# Main.net
KiCad netlist of a schematic drawn in Altium Designer
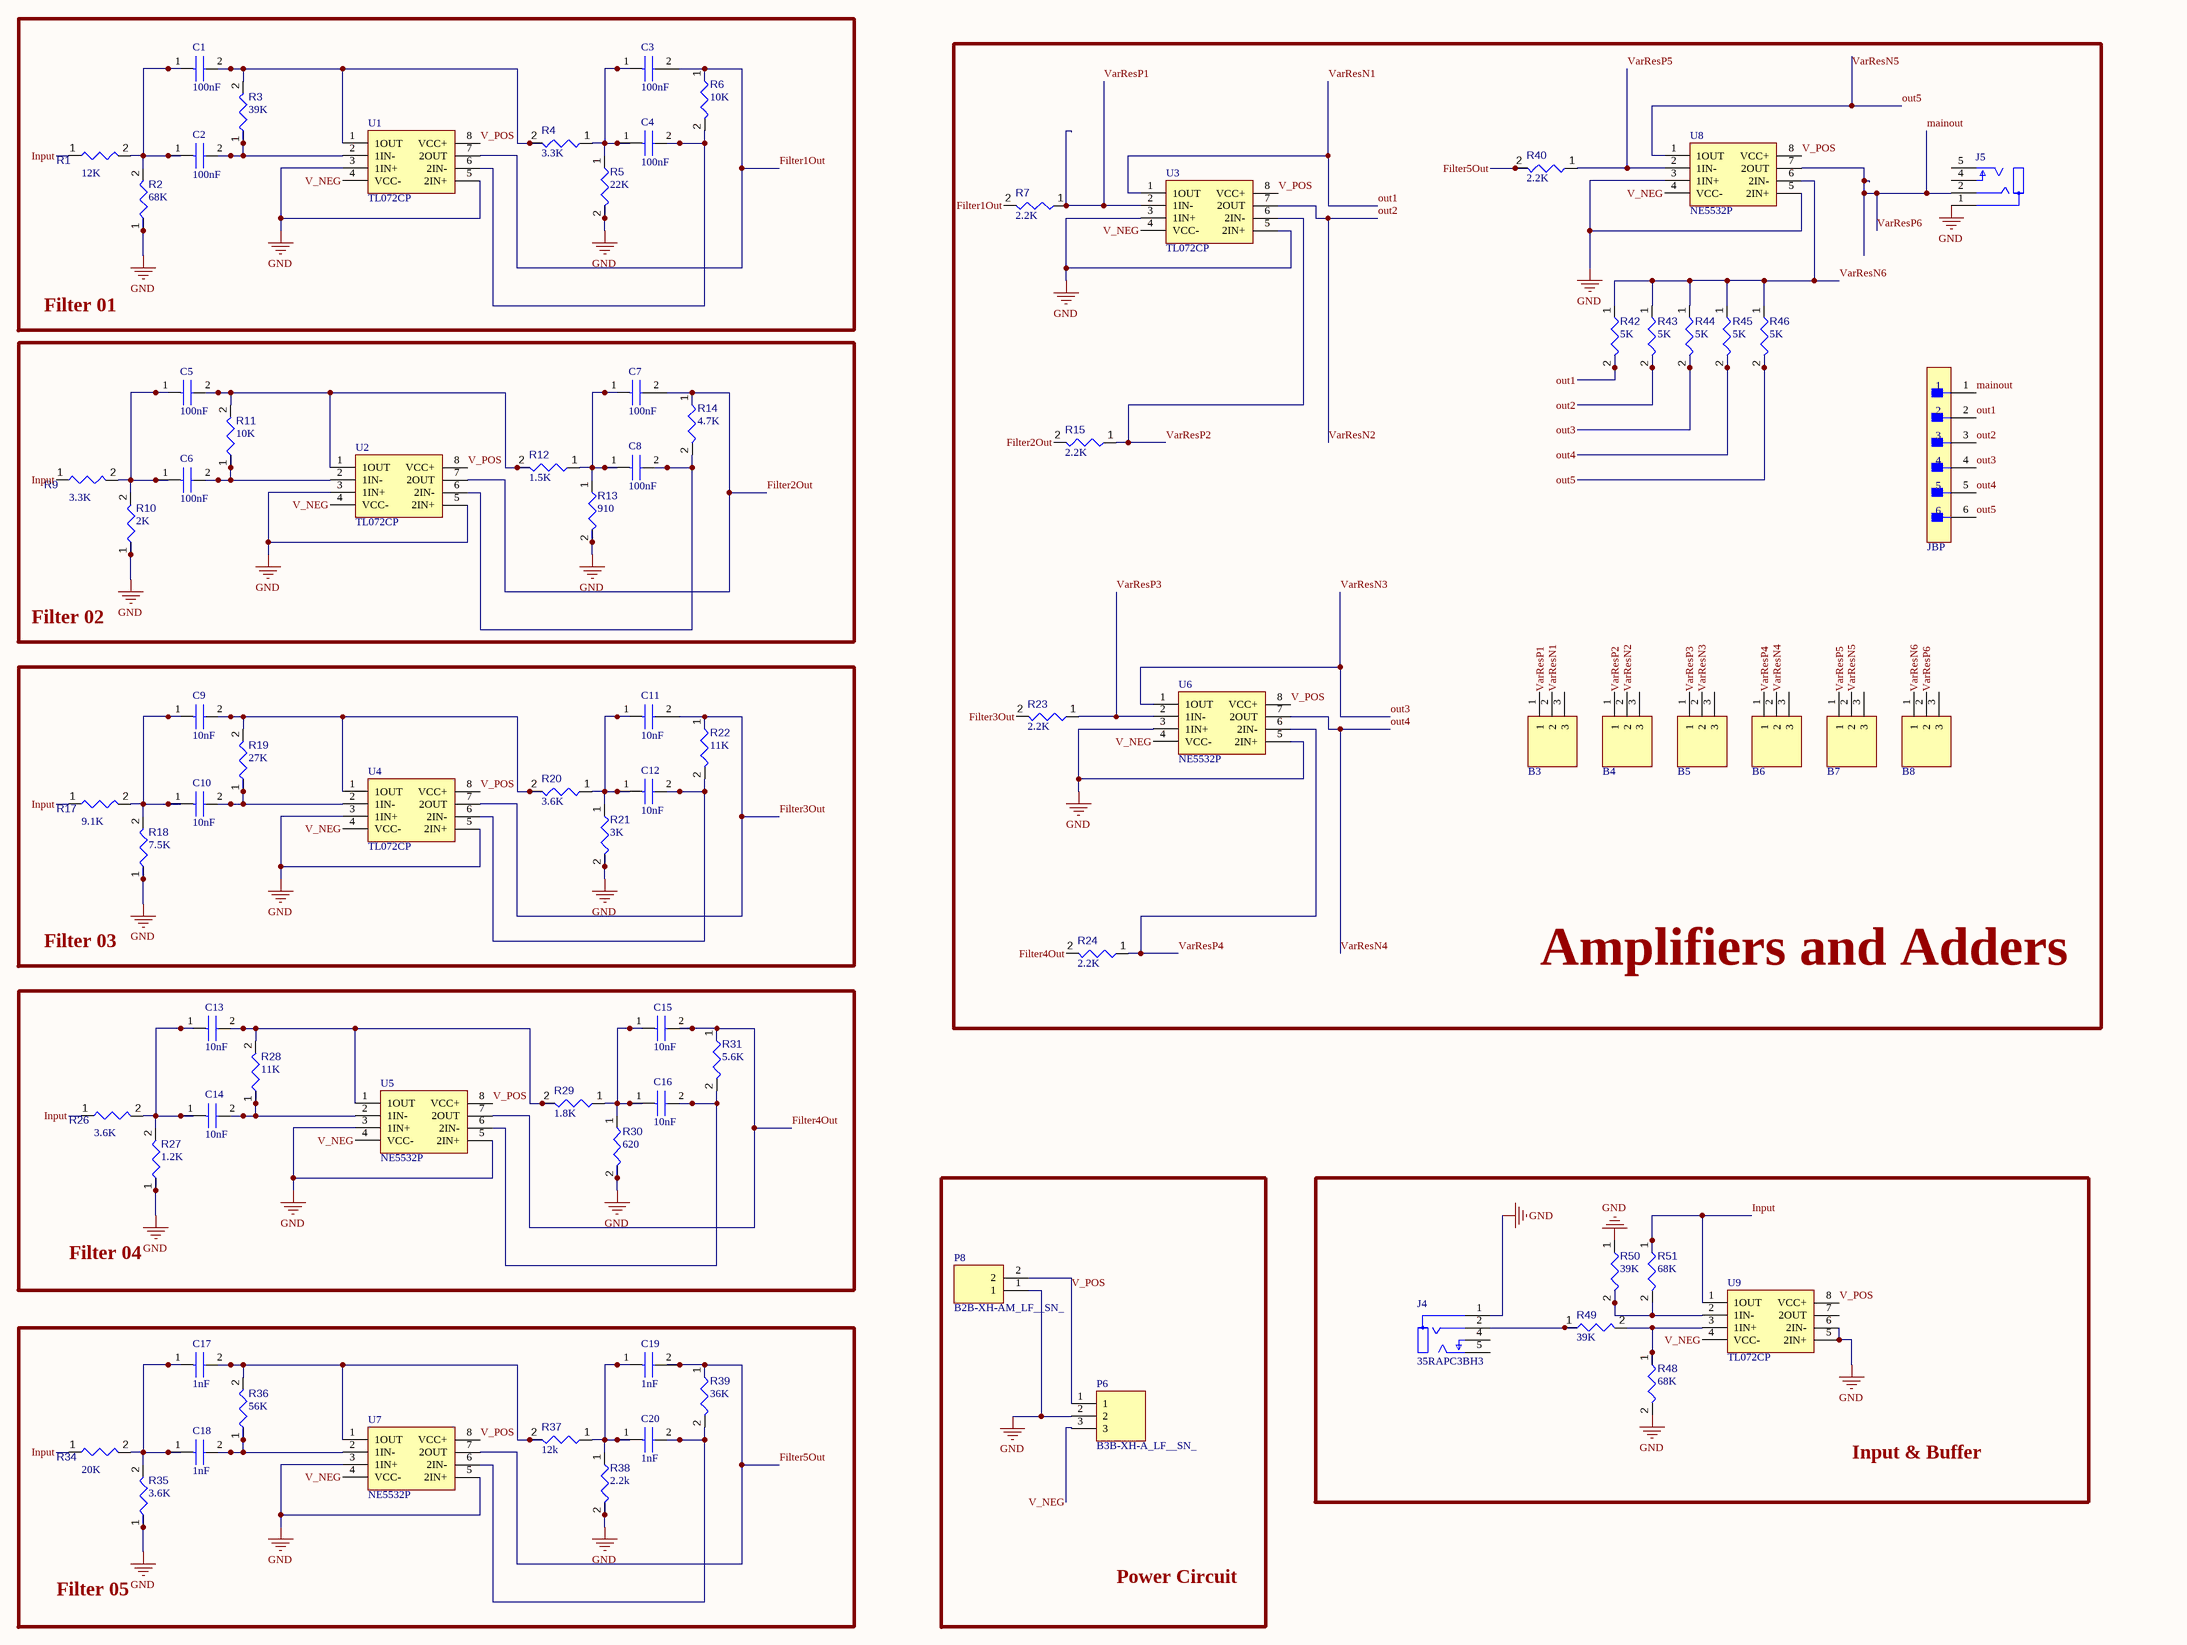
[diagram p0: Main.SchDoc]

(export (version "E")
  (design (tool "Eeschema 10.0.6"))
  (components
    (comp (ref "B3")
      (value "14910A0BHSX10502KA")
      (footprint "SamacSys:14910F0GJSX10103KA")
      (description "Variable Resistor")
      (fields (field (name "MOUSER PART NUMBER") "594-14910A0BHSP502KA"))
      (libsource (lib "*") (part "14910A0BHSX10502KA"))
    )
    (comp (ref "B4")
      (value "14910A0BHSX10502KA")
      (footprint "SamacSys:14910F0GJSX10103KA")
      (description "Variable Resistor")
      (fields (field (name "MOUSER PART NUMBER") "594-14910A0BHSP502KA"))
      (libsource (lib "*") (part "14910A0BHSX10502KA"))
    )
    (comp (ref "B5")
      (value "14910A0BHSX10502KA")
      (footprint "SamacSys:14910F0GJSX10103KA")
      (description "Variable Resistor")
      (fields (field (name "MOUSER PART NUMBER") "594-14910A0BHSP502KA"))
      (libsource (lib "*") (part "14910A0BHSX10502KA"))
    )
    (comp (ref "B6")
      (value "14910A0BHSX10502KA")
      (footprint "SamacSys:14910F0GJSX10103KA")
      (description "Variable Resistor")
      (fields (field (name "MOUSER PART NUMBER") "594-14910A0BHSP502KA"))
      (libsource (lib "*") (part "14910A0BHSX10502KA"))
    )
    (comp (ref "B7")
      (value "14910A0BHSX10502KA")
      (footprint "SamacSys:14910F0GJSX10103KA")
      (description "Variable Resistor")
      (fields (field (name "MOUSER PART NUMBER") "594-14910A0BHSP502KA"))
      (libsource (lib "*") (part "14910A0BHSX10502KA"))
    )
    (comp (ref "B8")
      (value "14910A0BHSX10502KA")
      (footprint "SamacSys:14910F0GJSX10103KA")
      (description "Variable Resistor")
      (fields (field (name "MOUSER PART NUMBER") "594-14910A0BHSP502KA"))
      (libsource (lib "*") (part "14910A0BHSX10502KA"))
    )
    (comp (ref "C1")
      (value "100nF")
      (footprint "SamacSys:K104K15X7RF5TL2")
      (description "Capacitor")
      (fields
        (field (name "MANUFACTURER_PART_NUMBER") "K104K15X7RF5TL2")
        (field (name "MOUSER PART NUMBER") "594-K104K15X7RF5TL2")
      )
      (libsource (lib "*") (part "K104K15X7RF5TL2"))
    )
    (comp (ref "C2")
      (value "100nF")
      (footprint "SamacSys:K104K15X7RF5TL2")
      (description "Capacitor")
      (fields
        (field (name "MANUFACTURER_PART_NUMBER") "K104K15X7RF5TL2")
        (field (name "MOUSER PART NUMBER") "594-K104K15X7RF5TL2")
      )
      (libsource (lib "*") (part "K104K15X7RF5TL2"))
    )
    (comp (ref "C3")
      (value "100nF")
      (footprint "SamacSys:K104K15X7RF5TL2")
      (description "Capacitor")
      (fields
        (field (name "MANUFACTURER_PART_NUMBER") "K104K15X7RF5TL2")
        (field (name "MOUSER PART NUMBER") "594-K104K15X7RF5TL2")
      )
      (libsource (lib "*") (part "K104K15X7RF5TL2"))
    )
    (comp (ref "C4")
      (value "100nF")
      (footprint "SamacSys:K104K15X7RF5TL2")
      (description "Capacitor")
      (fields
        (field (name "MANUFACTURER_PART_NUMBER") "K104K15X7RF5TL2")
        (field (name "MOUSER PART NUMBER") "594-K104K15X7RF5TL2")
      )
      (libsource (lib "*") (part "K104K15X7RF5TL2"))
    )
    (comp (ref "C5")
      (value "100nF")
      (footprint "SamacSys:K104K15X7RF5TL2")
      (description "Capacitor")
      (fields
        (field (name "MANUFACTURER_PART_NUMBER") "K104K15X7RF5TL2")
        (field (name "MOUSER PART NUMBER") "594-K104K15X7RF5TL2")
      )
      (libsource (lib "*") (part "K104K15X7RF5TL2"))
    )
    (comp (ref "C6")
      (value "100nF")
      (footprint "SamacSys:K104K15X7RF5TL2")
      (description "Capacitor")
      (fields
        (field (name "MANUFACTURER_PART_NUMBER") "K104K15X7RF5TL2")
        (field (name "MOUSER PART NUMBER") "594-K104K15X7RF5TL2")
      )
      (libsource (lib "*") (part "K104K15X7RF5TL2"))
    )
    (comp (ref "C7")
      (value "100nF")
      (footprint "SamacSys:K104K15X7RF5TL2")
      (description "Capacitor")
      (fields
        (field (name "MANUFACTURER_PART_NUMBER") "K104K15X7RF5TL2")
        (field (name "MOUSER PART NUMBER") "594-K104K15X7RF5TL2")
      )
      (libsource (lib "*") (part "K104K15X7RF5TL2"))
    )
    (comp (ref "C8")
      (value "100nF")
      (footprint "SamacSys:K104K15X7RF5TL2")
      (description "Capacitor")
      (fields
        (field (name "MANUFACTURER_PART_NUMBER") "K104K15X7RF5TL2")
        (field (name "MOUSER PART NUMBER") "594-K104K15X7RF5TL2")
      )
      (libsource (lib "*") (part "K104K15X7RF5TL2"))
    )
    (comp (ref "C9")
      (value "10nF")
      (footprint "SamacSys:K104K15X7RF5TL2")
      (description "Capacitor")
      (fields
        (field (name "MANUFACTURER_PART_NUMBER") "K104K15X7RF5TL2")
        (field (name "MOUSER PART NUMBER") "594-K104K15X7RF5TL2")
      )
      (libsource (lib "*") (part "K104K15X7RF5TL2"))
    )
    (comp (ref "C10")
      (value "10nF")
      (footprint "SamacSys:K104K15X7RF5TL2")
      (description "Capacitor")
      (fields
        (field (name "MANUFACTURER_PART_NUMBER") "K104K15X7RF5TL2")
        (field (name "MOUSER PART NUMBER") "594-K104K15X7RF5TL2")
      )
      (libsource (lib "*") (part "K104K15X7RF5TL2"))
    )
    (comp (ref "C11")
      (value "10nF")
      (footprint "SamacSys:K104K15X7RF5TL2")
      (description "Capacitor")
      (fields
        (field (name "MANUFACTURER_PART_NUMBER") "K104K15X7RF5TL2")
        (field (name "MOUSER PART NUMBER") "594-K104K15X7RF5TL2")
      )
      (libsource (lib "*") (part "K104K15X7RF5TL2"))
    )
    (comp (ref "C12")
      (value "10nF")
      (footprint "SamacSys:K104K15X7RF5TL2")
      (description "Capacitor")
      (fields
        (field (name "MANUFACTURER_PART_NUMBER") "K104K15X7RF5TL2")
        (field (name "MOUSER PART NUMBER") "594-K104K15X7RF5TL2")
      )
      (libsource (lib "*") (part "K104K15X7RF5TL2"))
    )
    (comp (ref "C13")
      (value "10nF")
      (footprint "SamacSys:K104K15X7RF5TL2")
      (description "Capacitor")
      (fields
        (field (name "MANUFACTURER_PART_NUMBER") "K104K15X7RF5TL2")
        (field (name "MOUSER PART NUMBER") "594-K104K15X7RF5TL2")
      )
      (libsource (lib "*") (part "K104K15X7RF5TL2"))
    )
    (comp (ref "C14")
      (value "10nF")
      (footprint "SamacSys:K104K15X7RF5TL2")
      (description "Capacitor")
      (fields
        (field (name "MANUFACTURER_PART_NUMBER") "K104K15X7RF5TL2")
        (field (name "MOUSER PART NUMBER") "594-K104K15X7RF5TL2")
      )
      (libsource (lib "*") (part "K104K15X7RF5TL2"))
    )
    (comp (ref "C15")
      (value "10nF")
      (footprint "SamacSys:K104K15X7RF5TL2")
      (description "Capacitor")
      (fields
        (field (name "MANUFACTURER_PART_NUMBER") "K104K15X7RF5TL2")
        (field (name "MOUSER PART NUMBER") "594-K104K15X7RF5TL2")
      )
      (libsource (lib "*") (part "K104K15X7RF5TL2"))
    )
    (comp (ref "C16")
      (value "10nF")
      (footprint "SamacSys:K104K15X7RF5TL2")
      (description "Capacitor")
      (fields
        (field (name "MANUFACTURER_PART_NUMBER") "K104K15X7RF5TL2")
        (field (name "MOUSER PART NUMBER") "594-K104K15X7RF5TL2")
      )
      (libsource (lib "*") (part "K104K15X7RF5TL2"))
    )
    (comp (ref "C17")
      (value "1nF")
      (footprint "SamacSys:K104K15X7RF5TL2")
      (description "Capacitor")
      (fields
        (field (name "MANUFACTURER_PART_NUMBER") "K104K15X7RF5TL2")
        (field (name "MOUSER PART NUMBER") "594-K104K15X7RF5TL2")
      )
      (libsource (lib "*") (part "K104K15X7RF5TL2"))
    )
    (comp (ref "C18")
      (value "1nF")
      (footprint "SamacSys:K104K15X7RF5TL2")
      (description "Capacitor")
      (fields
        (field (name "MANUFACTURER_PART_NUMBER") "K104K15X7RF5TL2")
        (field (name "MOUSER PART NUMBER") "594-K104K15X7RF5TL2")
      )
      (libsource (lib "*") (part "K104K15X7RF5TL2"))
    )
    (comp (ref "C19")
      (value "1nF")
      (footprint "SamacSys:K104K15X7RF5TL2")
      (description "Capacitor")
      (fields
        (field (name "MANUFACTURER_PART_NUMBER") "K104K15X7RF5TL2")
        (field (name "MOUSER PART NUMBER") "594-K104K15X7RF5TL2")
      )
      (libsource (lib "*") (part "K104K15X7RF5TL2"))
    )
    (comp (ref "C20")
      (value "1nF")
      (footprint "SamacSys:K104K15X7RF5TL2")
      (description "Capacitor")
      (fields
        (field (name "MANUFACTURER_PART_NUMBER") "K104K15X7RF5TL2")
        (field (name "MOUSER PART NUMBER") "594-K104K15X7RF5TL2")
      )
      (libsource (lib "*") (part "K104K15X7RF5TL2"))
    )
    (comp (ref "J4")
      (value "35RAPC3BH3")
      (footprint "FP-35RAPC3BH3-MFG")
      (description "CONN JACK STEREO 3.5MM R/A")
      (libsource (lib "Altium Content Vault") (part "6593a1246df2d7246a2ad7da18ee256"))
    )
    (comp (ref "J5")
      (value "35RAPC3BH3")
      (footprint "FP-35RAPC3BH3-MFG")
      (description "CONN JACK STEREO 3.5MM R/A")
      (libsource (lib "Altium Content Vault") (part "6593a1246df2d7246a2ad7da18ee256"))
    )
    (comp (ref "JBP")
      (value "B6B-XH-A(LF)(SN)")
      (footprint "FP-B6B-XH-A_LF_SN-MFG")
      (description "CONN HEADER VERT 6POS 2.5MM")
      (libsource (lib "Altium Content Vault") (part "f2cb566baf1c37ab5a3b8e90bbeafd6"))
    )
    (comp (ref "P6")
      (value "B3B-XH-A_LF__SN_")
      (footprint "SamacSys:B3BXHALFSN")
      (description "Connector")
      (fields (field (name "MANUFACTURER_PART_NUMBER") "B3B-XH-A(LF)(SN)"))
      (libsource (lib "*") (part "B3B-XH-A_LF__SN_"))
    )
    (comp (ref "P8")
      (value "B2B-XH-AM_LF__SN_")
      (footprint "SamacSys:B2BXHAMLFSN")
      (description "Connector")
      (fields (field (name "MANUFACTURER_PART_NUMBER") "B2B-XH-AM(LF)(SN)"))
      (libsource (lib "*") (part "B2B-XH-AM_LF__SN_"))
    )
    (comp (ref "R1")
      (value "12K")
      (footprint "RESA60-630X240")
      (description "Axial Resistor, 221 Ohm, +/- 1%, 250 mW, -55 to 155 degC, 2-Pin THD, RoHS, Bulk")
      (fields (field (name "TOLERANCE") "1%") (field (name "POWER") "250mW"))
      (libsource (lib "University of Moratuwa") (part "RES-2"))
    )
    (comp (ref "R2")
      (value "68K")
      (footprint "RESA60-630X240")
      (description "Axial Resistor, 221 Ohm, +/- 1%, 250 mW, -55 to 155 degC, 2-Pin THD, RoHS, Bulk")
      (fields (field (name "TOLERANCE") "1%") (field (name "POWER") "250mW"))
      (libsource (lib "University of Moratuwa") (part "RES-2"))
    )
    (comp (ref "R3")
      (value "39K")
      (footprint "RESA60-630X240")
      (description "Axial Resistor, 221 Ohm, +/- 1%, 250 mW, -55 to 155 degC, 2-Pin THD, RoHS, Bulk")
      (fields (field (name "TOLERANCE") "1%") (field (name "POWER") "250mW"))
      (libsource (lib "University of Moratuwa") (part "RES-2"))
    )
    (comp (ref "R4")
      (value "3.3K")
      (footprint "RESA60-630X240")
      (fields
        (field (name "TOLERANCE") "1%")
        (field (name "POWER") "250mW")
        (field (name "MANUFACTURER") "Yageo")
      )
      (libsource (lib "University of Moratuwa") (part "RES-2"))
    )
    (comp (ref "R5")
      (value "22K")
      (footprint "RESA60-630X240")
      (fields
        (field (name "TOLERANCE") "1%")
        (field (name "POWER") "250mW")
        (field (name "MANUFACTURER") "Yageo")
      )
      (libsource (lib "University of Moratuwa") (part "RES-2"))
    )
    (comp (ref "R6")
      (value "10K")
      (footprint "RESA60-630X240")
      (fields
        (field (name "TOLERANCE") "1%")
        (field (name "POWER") "250mW")
        (field (name "MANUFACTURER") "Yageo")
      )
      (libsource (lib "University of Moratuwa") (part "RES-2"))
    )
    (comp (ref "R7")
      (value "2.2K")
      (footprint "RESA60-630X240")
      (fields
        (field (name "TOLERANCE") "1%")
        (field (name "POWER") "250mW")
        (field (name "MANUFACTURER") "Yageo")
      )
      (libsource (lib "University of Moratuwa") (part "RES-2"))
    )
    (comp (ref "R9")
      (value "3.3K")
      (footprint "RESA60-630X240")
      (description "Axial Resistor, 221 Ohm, +/- 1%, 250 mW, -55 to 155 degC, 2-Pin THD, RoHS, Bulk")
      (fields (field (name "TOLERANCE") "1%") (field (name "POWER") "250mW"))
      (libsource (lib "University of Moratuwa") (part "RES-2"))
    )
    (comp (ref "R10")
      (value "2K")
      (footprint "RESA60-630X240")
      (description "Axial Resistor, 221 Ohm, +/- 1%, 250 mW, -55 to 155 degC, 2-Pin THD, RoHS, Bulk")
      (fields (field (name "TOLERANCE") "1%") (field (name "POWER") "250mW"))
      (libsource (lib "University of Moratuwa") (part "RES-2"))
    )
    (comp (ref "R11")
      (value "10K")
      (footprint "RESA60-630X240")
      (description "Axial Resistor, 221 Ohm, +/- 1%, 250 mW, -55 to 155 degC, 2-Pin THD, RoHS, Bulk")
      (fields (field (name "TOLERANCE") "1%") (field (name "POWER") "250mW"))
      (libsource (lib "University of Moratuwa") (part "RES-2"))
    )
    (comp (ref "R12")
      (value "1.5K")
      (footprint "RESA60-630X240")
      (fields
        (field (name "TOLERANCE") "1%")
        (field (name "POWER") "250mW")
        (field (name "MANUFACTURER") "Yageo")
      )
      (libsource (lib "University of Moratuwa") (part "RES-2"))
    )
    (comp (ref "R13")
      (value "910")
      (footprint "RESA60-630X240")
      (fields
        (field (name "TOLERANCE") "1%")
        (field (name "POWER") "250mW")
        (field (name "MANUFACTURER") "Yageo")
      )
      (libsource (lib "University of Moratuwa") (part "RES-2"))
    )
    (comp (ref "R14")
      (value "4.7K")
      (footprint "RESA60-630X240")
      (fields
        (field (name "TOLERANCE") "1%")
        (field (name "POWER") "250mW")
        (field (name "MANUFACTURER") "Yageo")
      )
      (libsource (lib "University of Moratuwa") (part "RES-2"))
    )
    (comp (ref "R15")
      (value "2.2K")
      (footprint "RESA60-630X240")
      (fields
        (field (name "TOLERANCE") "1%")
        (field (name "POWER") "250mW")
        (field (name "MANUFACTURER") "Yageo")
      )
      (libsource (lib "University of Moratuwa") (part "RES-2"))
    )
    (comp (ref "R17")
      (value "9.1K")
      (footprint "RESA60-630X240")
      (description "Axial Resistor, 221 Ohm, +/- 1%, 250 mW, -55 to 155 degC, 2-Pin THD, RoHS, Bulk")
      (fields (field (name "TOLERANCE") "1%") (field (name "POWER") "250mW"))
      (libsource (lib "University of Moratuwa") (part "RES-2"))
    )
    (comp (ref "R18")
      (value "7.5K")
      (footprint "RESA60-630X240")
      (description "Axial Resistor, 221 Ohm, +/- 1%, 250 mW, -55 to 155 degC, 2-Pin THD, RoHS, Bulk")
      (fields (field (name "TOLERANCE") "1%") (field (name "POWER") "250mW"))
      (libsource (lib "University of Moratuwa") (part "RES-2"))
    )
    (comp (ref "R19")
      (value "27K")
      (footprint "RESA60-630X240")
      (description "Axial Resistor, 221 Ohm, +/- 1%, 250 mW, -55 to 155 degC, 2-Pin THD, RoHS, Bulk")
      (fields (field (name "TOLERANCE") "1%") (field (name "POWER") "250mW"))
      (libsource (lib "University of Moratuwa") (part "RES-2"))
    )
    (comp (ref "R20")
      (value "3.6K")
      (footprint "RESA60-630X240")
      (fields
        (field (name "TOLERANCE") "1%")
        (field (name "POWER") "250mW")
        (field (name "MANUFACTURER") "Yageo")
      )
      (libsource (lib "University of Moratuwa") (part "RES-2"))
    )
    (comp (ref "R21")
      (value "3K")
      (footprint "RESA60-630X240")
      (fields
        (field (name "TOLERANCE") "1%")
        (field (name "POWER") "250mW")
        (field (name "MANUFACTURER") "Yageo")
      )
      (libsource (lib "University of Moratuwa") (part "RES-2"))
    )
    (comp (ref "R22")
      (value "11K")
      (footprint "RESA60-630X240")
      (fields
        (field (name "TOLERANCE") "1%")
        (field (name "POWER") "250mW")
        (field (name "MANUFACTURER") "Yageo")
      )
      (libsource (lib "University of Moratuwa") (part "RES-2"))
    )
    (comp (ref "R23")
      (value "2.2K")
      (footprint "RESA60-630X240")
      (fields
        (field (name "TOLERANCE") "1%")
        (field (name "POWER") "250mW")
        (field (name "MANUFACTURER") "Yageo")
      )
      (libsource (lib "University of Moratuwa") (part "RES-2"))
    )
    (comp (ref "R24")
      (value "2.2K")
      (footprint "RESA60-630X240")
      (fields
        (field (name "TOLERANCE") "1%")
        (field (name "POWER") "250mW")
        (field (name "MANUFACTURER") "Yageo")
      )
      (libsource (lib "University of Moratuwa") (part "RES-2"))
    )
    (comp (ref "R26")
      (value "3.6K")
      (footprint "RESA60-630X240")
      (description "Axial Resistor, 221 Ohm, +/- 1%, 250 mW, -55 to 155 degC, 2-Pin THD, RoHS, Bulk")
      (fields (field (name "TOLERANCE") "1%") (field (name "POWER") "250mW"))
      (libsource (lib "University of Moratuwa") (part "RES-2"))
    )
    (comp (ref "R27")
      (value "1.2K")
      (footprint "RESA60-630X240")
      (description "Axial Resistor, 221 Ohm, +/- 1%, 250 mW, -55 to 155 degC, 2-Pin THD, RoHS, Bulk")
      (fields (field (name "TOLERANCE") "1%") (field (name "POWER") "250mW"))
      (libsource (lib "University of Moratuwa") (part "RES-2"))
    )
    (comp (ref "R28")
      (value "11K")
      (footprint "RESA60-630X240")
      (description "Axial Resistor, 221 Ohm, +/- 1%, 250 mW, -55 to 155 degC, 2-Pin THD, RoHS, Bulk")
      (fields (field (name "TOLERANCE") "1%") (field (name "POWER") "250mW"))
      (libsource (lib "University of Moratuwa") (part "RES-2"))
    )
    (comp (ref "R29")
      (value "1.8K")
      (footprint "RESA60-630X240")
      (fields
        (field (name "TOLERANCE") "1%")
        (field (name "POWER") "250mW")
        (field (name "MANUFACTURER") "Yageo")
      )
      (libsource (lib "University of Moratuwa") (part "RES-2"))
    )
    (comp (ref "R30")
      (value "620")
      (footprint "RESA60-630X240")
      (fields
        (field (name "TOLERANCE") "1%")
        (field (name "POWER") "250mW")
        (field (name "MANUFACTURER") "Yageo")
      )
      (libsource (lib "University of Moratuwa") (part "RES-2"))
    )
    (comp (ref "R31")
      (value "5.6K")
      (footprint "RESA60-630X240")
      (fields
        (field (name "TOLERANCE") "1%")
        (field (name "POWER") "250mW")
        (field (name "MANUFACTURER") "Yageo")
      )
      (libsource (lib "University of Moratuwa") (part "RES-2"))
    )
    (comp (ref "R34")
      (value "20K")
      (footprint "RESA60-630X240")
      (description "Axial Resistor, 221 Ohm, +/- 1%, 250 mW, -55 to 155 degC, 2-Pin THD, RoHS, Bulk")
      (fields (field (name "TOLERANCE") "1%") (field (name "POWER") "250mW"))
      (libsource (lib "University of Moratuwa") (part "RES-2"))
    )
    (comp (ref "R35")
      (value "3.6K")
      (footprint "RESA60-630X240")
      (description "Axial Resistor, 221 Ohm, +/- 1%, 250 mW, -55 to 155 degC, 2-Pin THD, RoHS, Bulk")
      (fields (field (name "TOLERANCE") "1%") (field (name "POWER") "250mW"))
      (libsource (lib "University of Moratuwa") (part "RES-2"))
    )
    (comp (ref "R36")
      (value "56K")
      (footprint "RESA60-630X240")
      (description "Axial Resistor, 221 Ohm, +/- 1%, 250 mW, -55 to 155 degC, 2-Pin THD, RoHS, Bulk")
      (fields (field (name "TOLERANCE") "1%") (field (name "POWER") "250mW"))
      (libsource (lib "University of Moratuwa") (part "RES-2"))
    )
    (comp (ref "R37")
      (value "12k")
      (footprint "RESA60-630X240")
      (fields
        (field (name "TOLERANCE") "1%")
        (field (name "POWER") "250mW")
        (field (name "MANUFACTURER") "Yageo")
      )
      (libsource (lib "University of Moratuwa") (part "RES-2"))
    )
    (comp (ref "R38")
      (value "2.2k")
      (footprint "RESA60-630X240")
      (fields
        (field (name "TOLERANCE") "1%")
        (field (name "POWER") "250mW")
        (field (name "MANUFACTURER") "Yageo")
      )
      (libsource (lib "University of Moratuwa") (part "RES-2"))
    )
    (comp (ref "R39")
      (value "36K")
      (footprint "RESA60-630X240")
      (fields
        (field (name "TOLERANCE") "1%")
        (field (name "POWER") "250mW")
        (field (name "MANUFACTURER") "Yageo")
      )
      (libsource (lib "University of Moratuwa") (part "RES-2"))
    )
    (comp (ref "R40")
      (value "2.2K")
      (footprint "RESA60-630X240")
      (fields
        (field (name "TOLERANCE") "1%")
        (field (name "POWER") "250mW")
        (field (name "MANUFACTURER") "Yageo")
      )
      (libsource (lib "University of Moratuwa") (part "RES-2"))
    )
    (comp (ref "R42")
      (value "5K")
      (footprint "RESA60-630X240")
      (fields
        (field (name "TOLERANCE") "1%")
        (field (name "POWER") "250mW")
        (field (name "MANUFACTURER") "Yageo")
      )
      (libsource (lib "University of Moratuwa") (part "RES-2"))
    )
    (comp (ref "R43")
      (value "5K")
      (footprint "RESA60-630X240")
      (fields
        (field (name "TOLERANCE") "1%")
        (field (name "POWER") "250mW")
        (field (name "MANUFACTURER") "Yageo")
      )
      (libsource (lib "University of Moratuwa") (part "RES-2"))
    )
    (comp (ref "R44")
      (value "5K")
      (footprint "RESA60-630X240")
      (fields
        (field (name "TOLERANCE") "1%")
        (field (name "POWER") "250mW")
        (field (name "MANUFACTURER") "Yageo")
      )
      (libsource (lib "University of Moratuwa") (part "RES-2"))
    )
    (comp (ref "R45")
      (value "5K")
      (footprint "RESA60-630X240")
      (fields
        (field (name "TOLERANCE") "1%")
        (field (name "POWER") "250mW")
        (field (name "MANUFACTURER") "Yageo")
      )
      (libsource (lib "University of Moratuwa") (part "RES-2"))
    )
    (comp (ref "R46")
      (value "5K")
      (footprint "RESA60-630X240")
      (fields
        (field (name "TOLERANCE") "1%")
        (field (name "POWER") "250mW")
        (field (name "MANUFACTURER") "Yageo")
      )
      (libsource (lib "University of Moratuwa") (part "RES-2"))
    )
    (comp (ref "R48")
      (value "68K")
      (footprint "RESA60-630X240")
      (fields
        (field (name "TOLERANCE") "1%")
        (field (name "POWER") "250mW")
        (field (name "MANUFACTURER") "Yageo")
      )
      (libsource (lib "University of Moratuwa") (part "RES-2"))
    )
    (comp (ref "R49")
      (value "39K")
      (footprint "RESA60-630X240")
      (fields
        (field (name "TOLERANCE") "1%")
        (field (name "POWER") "250mW")
        (field (name "MANUFACTURER") "Yageo")
      )
      (libsource (lib "University of Moratuwa") (part "RES-2"))
    )
    (comp (ref "R50")
      (value "39K")
      (footprint "RESA60-630X240")
      (fields
        (field (name "TOLERANCE") "1%")
        (field (name "POWER") "250mW")
        (field (name "MANUFACTURER") "Yageo")
      )
      (libsource (lib "University of Moratuwa") (part "RES-2"))
    )
    (comp (ref "R51")
      (value "68K")
      (footprint "RESA60-630X240")
      (fields
        (field (name "TOLERANCE") "1%")
        (field (name "POWER") "250mW")
        (field (name "MANUFACTURER") "Yageo")
      )
      (libsource (lib "University of Moratuwa") (part "RES-2"))
    )
    (comp (ref "U1")
      (value "TL072CP")
      (footprint "SamacSys:DIP794W53P254L959H508Q8N")
      (description "Integrated Circuit")
      (fields (field (name "MOUSER PART NUMBER") "595-TL072CP"))
      (libsource (lib "*") (part "TL072CP"))
    )
    (comp (ref "U2")
      (value "TL072CP")
      (footprint "SamacSys:DIP794W53P254L959H508Q8N")
      (description "Integrated Circuit")
      (fields (field (name "MOUSER PART NUMBER") "595-TL072CP"))
      (libsource (lib "*") (part "TL072CP"))
    )
    (comp (ref "U3")
      (value "TL072CP")
      (footprint "SamacSys:DIP794W53P254L959H508Q8N")
      (description "Integrated Circuit")
      (fields (field (name "MOUSER PART NUMBER") "595-TL072CP"))
      (libsource (lib "*") (part "TL072CP"))
    )
    (comp (ref "U4")
      (value "TL072CP")
      (footprint "SamacSys:DIP794W53P254L959H508Q8N")
      (description "Integrated Circuit")
      (fields (field (name "MOUSER PART NUMBER") "595-TL072CP"))
      (libsource (lib "*") (part "TL072CP"))
    )
    (comp (ref "U5")
      (value "NE5532P")
      (footprint "SamacSys:DIP794W53P254L959H508Q8N")
      (description "Integrated Circuit")
      (fields (field (name "MOUSER PART NUMBER") "595-NE5532P"))
      (libsource (lib "*") (part "NE5532P"))
    )
    (comp (ref "U6")
      (value "NE5532P")
      (footprint "SamacSys:DIP794W53P254L959H508Q8N")
      (description "Integrated Circuit")
      (fields (field (name "MOUSER PART NUMBER") "595-NE5532P"))
      (libsource (lib "*") (part "NE5532P"))
    )
    (comp (ref "U7")
      (value "NE5532P")
      (footprint "SamacSys:DIP794W53P254L959H508Q8N")
      (description "Integrated Circuit")
      (fields (field (name "MOUSER PART NUMBER") "595-NE5532P"))
      (libsource (lib "*") (part "NE5532P"))
    )
    (comp (ref "U8")
      (value "NE5532P")
      (footprint "SamacSys:DIP794W53P254L959H508Q8N")
      (description "Integrated Circuit")
      (fields (field (name "MOUSER PART NUMBER") "595-NE5532P"))
      (libsource (lib "*") (part "NE5532P"))
    )
    (comp (ref "U9")
      (value "TL072CP")
      (footprint "SamacSys:DIP794W53P254L959H508Q8N")
      (description "Integrated Circuit")
      (fields (field (name "MOUSER PART NUMBER") "595-TL072CP"))
      (libsource (lib "*") (part "TL072CP"))
    )
  )
  (nets
    (net (code "1") (name "/Filter1Out") (class "Default")
      (node (ref "C3") (pin "2") (pinfunction "-_2") (pintype "passive"))
      (node (ref "R6") (pin "1") (pinfunction "1_1") (pintype "passive"))
      (node (ref "R7") (pin "2") (pinfunction "2_2") (pintype "passive"))
      (node (ref "U1") (pin "7") (pinfunction "2OUT_7") (pintype "passive"))
    )
    (net (code "2") (name "/Filter2Out") (class "Default")
      (node (ref "C7") (pin "2") (pinfunction "-_2") (pintype "passive"))
      (node (ref "R14") (pin "1") (pinfunction "1_1") (pintype "passive"))
      (node (ref "R15") (pin "2") (pinfunction "2_2") (pintype "passive"))
      (node (ref "U2") (pin "7") (pinfunction "2OUT_7") (pintype "passive"))
    )
    (net (code "3") (name "/Filter3Out") (class "Default")
      (node (ref "C11") (pin "2") (pinfunction "-_2") (pintype "passive"))
      (node (ref "R22") (pin "1") (pinfunction "1_1") (pintype "passive"))
      (node (ref "R23") (pin "2") (pinfunction "2_2") (pintype "passive"))
      (node (ref "U4") (pin "7") (pinfunction "2OUT_7") (pintype "passive"))
    )
    (net (code "4") (name "/Filter4Out") (class "Default")
      (node (ref "C15") (pin "2") (pinfunction "-_2") (pintype "passive"))
      (node (ref "R24") (pin "2") (pinfunction "2_2") (pintype "passive"))
      (node (ref "R31") (pin "1") (pinfunction "1_1") (pintype "passive"))
      (node (ref "U5") (pin "7") (pinfunction "2OUT_7") (pintype "passive"))
    )
    (net (code "5") (name "/Filter5Out") (class "Default")
      (node (ref "C19") (pin "2") (pinfunction "-_2") (pintype "passive"))
      (node (ref "R39") (pin "1") (pinfunction "1_1") (pintype "passive"))
      (node (ref "R40") (pin "2") (pinfunction "2_2") (pintype "passive"))
      (node (ref "U7") (pin "7") (pinfunction "2OUT_7") (pintype "passive"))
    )
    (net (code "6") (name "/Input") (class "Default")
      (node (ref "R1") (pin "1") (pinfunction "1_1") (pintype "passive"))
      (node (ref "R17") (pin "1") (pinfunction "1_1") (pintype "passive"))
      (node (ref "R26") (pin "1") (pinfunction "1_1") (pintype "passive"))
      (node (ref "R34") (pin "1") (pinfunction "1_1") (pintype "passive"))
      (node (ref "R51") (pin "1") (pinfunction "1_1") (pintype "passive"))
      (node (ref "R9") (pin "1") (pinfunction "1_1") (pintype "passive"))
      (node (ref "U9") (pin "1") (pinfunction "1OUT_1") (pintype "passive"))
    )
    (net (code "7") (name "/V_NEG") (class "Default")
      (node (ref "P6") (pin "3") (pinfunction "3_3") (pintype "passive"))
      (node (ref "U1") (pin "4") (pinfunction "VCC-_4") (pintype "passive"))
      (node (ref "U2") (pin "4") (pinfunction "VCC-_4") (pintype "passive"))
      (node (ref "U3") (pin "4") (pinfunction "VCC-_4") (pintype "passive"))
      (node (ref "U4") (pin "4") (pinfunction "VCC-_4") (pintype "passive"))
      (node (ref "U5") (pin "4") (pinfunction "VCC-_4") (pintype "passive"))
      (node (ref "U6") (pin "4") (pinfunction "VCC-_4") (pintype "passive"))
      (node (ref "U7") (pin "4") (pinfunction "VCC-_4") (pintype "passive"))
      (node (ref "U8") (pin "4") (pinfunction "VCC-_4") (pintype "passive"))
      (node (ref "U9") (pin "4") (pinfunction "VCC-_4") (pintype "passive"))
    )
    (net (code "8") (name "/V_POS") (class "Default")
      (node (ref "P6") (pin "1") (pinfunction "1_1") (pintype "passive"))
      (node (ref "P8") (pin "2") (pinfunction "2_2") (pintype "passive"))
      (node (ref "U1") (pin "8") (pinfunction "VCC+_8") (pintype "passive"))
      (node (ref "U2") (pin "8") (pinfunction "VCC+_8") (pintype "passive"))
      (node (ref "U3") (pin "8") (pinfunction "VCC+_8") (pintype "passive"))
      (node (ref "U4") (pin "8") (pinfunction "VCC+_8") (pintype "passive"))
      (node (ref "U5") (pin "8") (pinfunction "VCC+_8") (pintype "passive"))
      (node (ref "U6") (pin "8") (pinfunction "VCC+_8") (pintype "passive"))
      (node (ref "U7") (pin "8") (pinfunction "VCC+_8") (pintype "passive"))
      (node (ref "U8") (pin "8") (pinfunction "VCC+_8") (pintype "passive"))
      (node (ref "U9") (pin "8") (pinfunction "VCC+_8") (pintype "passive"))
    )
    (net (code "9") (name "/VarResN1") (class "Default")
      (node (ref "B3") (pin "2") (pinfunction "2_2") (pintype "passive"))
      (node (ref "JBP") (pin "2") (pinfunction "2_2") (pintype "passive"))
      (node (ref "R42") (pin "2") (pinfunction "2_2") (pintype "passive"))
      (node (ref "U3") (pin "1") (pinfunction "1OUT_1") (pintype "passive"))
    )
    (net (code "10") (name "/VarResN2") (class "Default")
      (node (ref "B4") (pin "2") (pinfunction "2_2") (pintype "passive"))
      (node (ref "JBP") (pin "3") (pinfunction "3_3") (pintype "passive"))
      (node (ref "R43") (pin "2") (pinfunction "2_2") (pintype "passive"))
      (node (ref "U3") (pin "7") (pinfunction "2OUT_7") (pintype "passive"))
    )
    (net (code "11") (name "/VarResN3") (class "Default")
      (node (ref "B5") (pin "2") (pinfunction "2_2") (pintype "passive"))
      (node (ref "JBP") (pin "4") (pinfunction "4_4") (pintype "passive"))
      (node (ref "R44") (pin "2") (pinfunction "2_2") (pintype "passive"))
      (node (ref "U6") (pin "1") (pinfunction "1OUT_1") (pintype "passive"))
    )
    (net (code "12") (name "/VarResN4") (class "Default")
      (node (ref "B6") (pin "2") (pinfunction "2_2") (pintype "passive"))
      (node (ref "JBP") (pin "5") (pinfunction "5_5") (pintype "passive"))
      (node (ref "R45") (pin "2") (pinfunction "2_2") (pintype "passive"))
      (node (ref "U6") (pin "7") (pinfunction "2OUT_7") (pintype "passive"))
    )
    (net (code "13") (name "/VarResN5") (class "Default")
      (node (ref "B7") (pin "2") (pinfunction "2_2") (pintype "passive"))
      (node (ref "JBP") (pin "6") (pinfunction "6_6") (pintype "passive"))
      (node (ref "R46") (pin "2") (pinfunction "2_2") (pintype "passive"))
      (node (ref "U8") (pin "1") (pinfunction "1OUT_1") (pintype "passive"))
    )
    (net (code "14") (name "/VarResN6") (class "Default")
      (node (ref "B8") (pin "1") (pinfunction "1_1") (pintype "passive"))
      (node (ref "R42") (pin "1") (pinfunction "1_1") (pintype "passive"))
      (node (ref "R43") (pin "1") (pinfunction "1_1") (pintype "passive"))
      (node (ref "R44") (pin "1") (pinfunction "1_1") (pintype "passive"))
      (node (ref "R45") (pin "1") (pinfunction "1_1") (pintype "passive"))
      (node (ref "R46") (pin "1") (pinfunction "1_1") (pintype "passive"))
      (node (ref "U8") (pin "6") (pinfunction "2IN-_6") (pintype "passive"))
    )
    (net (code "15") (name "/VarResP1") (class "Default")
      (node (ref "B3") (pin "1") (pinfunction "1_1") (pintype "passive"))
      (node (ref "R7") (pin "1") (pinfunction "1_1") (pintype "passive"))
      (node (ref "U3") (pin "2") (pinfunction "1IN-_2") (pintype "passive"))
    )
    (net (code "16") (name "/VarResP2") (class "Default")
      (node (ref "B4") (pin "1") (pinfunction "1_1") (pintype "passive"))
      (node (ref "R15") (pin "1") (pinfunction "1_1") (pintype "passive"))
      (node (ref "U3") (pin "6") (pinfunction "2IN-_6") (pintype "passive"))
    )
    (net (code "17") (name "/VarResP3") (class "Default")
      (node (ref "B5") (pin "1") (pinfunction "1_1") (pintype "passive"))
      (node (ref "R23") (pin "1") (pinfunction "1_1") (pintype "passive"))
      (node (ref "U6") (pin "2") (pinfunction "1IN-_2") (pintype "passive"))
    )
    (net (code "18") (name "/VarResP4") (class "Default")
      (node (ref "B6") (pin "1") (pinfunction "1_1") (pintype "passive"))
      (node (ref "R24") (pin "1") (pinfunction "1_1") (pintype "passive"))
      (node (ref "U6") (pin "6") (pinfunction "2IN-_6") (pintype "passive"))
    )
    (net (code "19") (name "/VarResP5") (class "Default")
      (node (ref "B7") (pin "1") (pinfunction "1_1") (pintype "passive"))
      (node (ref "R40") (pin "1") (pinfunction "1_1") (pintype "passive"))
      (node (ref "U8") (pin "2") (pinfunction "1IN-_2") (pintype "passive"))
    )
    (net (code "20") (name "/VarResP6") (class "Default")
      (node (ref "B8") (pin "2") (pinfunction "2_2") (pintype "passive"))
      (node (ref "J5") (pin "2") (pinfunction "2_2") (pintype "passive"))
      (node (ref "JBP") (pin "1") (pinfunction "1_1") (pintype "passive"))
      (node (ref "U8") (pin "7") (pinfunction "2OUT_7") (pintype "passive"))
    )
    (net (code "21") (name "GND") (class "Default")
      (node (ref "J4") (pin "1") (pinfunction "1_1") (pintype "passive"))
      (node (ref "J5") (pin "1") (pinfunction "1_1") (pintype "passive"))
      (node (ref "P6") (pin "2") (pinfunction "2_2") (pintype "passive"))
      (node (ref "P8") (pin "1") (pinfunction "1_1") (pintype "passive"))
      (node (ref "R10") (pin "1") (pinfunction "1_1") (pintype "passive"))
      (node (ref "R13") (pin "2") (pinfunction "2_2") (pintype "passive"))
      (node (ref "R18") (pin "1") (pinfunction "1_1") (pintype "passive"))
      (node (ref "R2") (pin "1") (pinfunction "1_1") (pintype "passive"))
      (node (ref "R21") (pin "2") (pinfunction "2_2") (pintype "passive"))
      (node (ref "R27") (pin "1") (pinfunction "1_1") (pintype "passive"))
      (node (ref "R30") (pin "2") (pinfunction "2_2") (pintype "passive"))
      (node (ref "R35") (pin "1") (pinfunction "1_1") (pintype "passive"))
      (node (ref "R38") (pin "2") (pinfunction "2_2") (pintype "passive"))
      (node (ref "R48") (pin "2") (pinfunction "2_2") (pintype "passive"))
      (node (ref "R5") (pin "2") (pinfunction "2_2") (pintype "passive"))
      (node (ref "R50") (pin "1") (pinfunction "1_1") (pintype "passive"))
      (node (ref "U1") (pin "3") (pinfunction "1IN+_3") (pintype "passive"))
      (node (ref "U1") (pin "5") (pinfunction "2IN+_5") (pintype "passive"))
      (node (ref "U2") (pin "3") (pinfunction "1IN+_3") (pintype "passive"))
      (node (ref "U2") (pin "5") (pinfunction "2IN+_5") (pintype "passive"))
      (node (ref "U3") (pin "3") (pinfunction "1IN+_3") (pintype "passive"))
      (node (ref "U3") (pin "5") (pinfunction "2IN+_5") (pintype "passive"))
      (node (ref "U4") (pin "3") (pinfunction "1IN+_3") (pintype "passive"))
      (node (ref "U4") (pin "5") (pinfunction "2IN+_5") (pintype "passive"))
      (node (ref "U5") (pin "3") (pinfunction "1IN+_3") (pintype "passive"))
      (node (ref "U5") (pin "5") (pinfunction "2IN+_5") (pintype "passive"))
      (node (ref "U6") (pin "3") (pinfunction "1IN+_3") (pintype "passive"))
      (node (ref "U6") (pin "5") (pinfunction "2IN+_5") (pintype "passive"))
      (node (ref "U7") (pin "3") (pinfunction "1IN+_3") (pintype "passive"))
      (node (ref "U7") (pin "5") (pinfunction "2IN+_5") (pintype "passive"))
      (node (ref "U8") (pin "3") (pinfunction "1IN+_3") (pintype "passive"))
      (node (ref "U8") (pin "5") (pinfunction "2IN+_5") (pintype "passive"))
      (node (ref "U9") (pin "5") (pinfunction "2IN+_5") (pintype "passive"))
      (node (ref "U9") (pin "6") (pinfunction "2IN-_6") (pintype "passive"))
    )
    (net (code "22") (name "Net-(C1-+)") (class "Default")
      (node (ref "C1") (pin "1") (pinfunction "+_1") (pintype "passive"))
      (node (ref "C2") (pin "1") (pinfunction "+_1") (pintype "passive"))
      (node (ref "R1") (pin "2") (pinfunction "2_2") (pintype "passive"))
      (node (ref "R2") (pin "2") (pinfunction "2_2") (pintype "passive"))
    )
    (net (code "23") (name "Net-(C1--)") (class "Default")
      (node (ref "C1") (pin "2") (pinfunction "-_2") (pintype "passive"))
      (node (ref "R3") (pin "2") (pinfunction "2_2") (pintype "passive"))
      (node (ref "R4") (pin "2") (pinfunction "2_2") (pintype "passive"))
      (node (ref "U1") (pin "1") (pinfunction "1OUT_1") (pintype "passive"))
    )
    (net (code "24") (name "Net-(C2--)") (class "Default")
      (node (ref "C2") (pin "2") (pinfunction "-_2") (pintype "passive"))
      (node (ref "R3") (pin "1") (pinfunction "1_1") (pintype "passive"))
      (node (ref "U1") (pin "2") (pinfunction "1IN-_2") (pintype "passive"))
    )
    (net (code "25") (name "Net-(C3-+)") (class "Default")
      (node (ref "C3") (pin "1") (pinfunction "+_1") (pintype "passive"))
      (node (ref "C4") (pin "1") (pinfunction "+_1") (pintype "passive"))
      (node (ref "R4") (pin "1") (pinfunction "1_1") (pintype "passive"))
      (node (ref "R5") (pin "1") (pinfunction "1_1") (pintype "passive"))
    )
    (net (code "26") (name "Net-(C4--)") (class "Default")
      (node (ref "C4") (pin "2") (pinfunction "-_2") (pintype "passive"))
      (node (ref "R6") (pin "2") (pinfunction "2_2") (pintype "passive"))
      (node (ref "U1") (pin "6") (pinfunction "2IN-_6") (pintype "passive"))
    )
    (net (code "27") (name "Net-(C5-+)") (class "Default")
      (node (ref "C5") (pin "1") (pinfunction "+_1") (pintype "passive"))
      (node (ref "C6") (pin "1") (pinfunction "+_1") (pintype "passive"))
      (node (ref "R10") (pin "2") (pinfunction "2_2") (pintype "passive"))
      (node (ref "R9") (pin "2") (pinfunction "2_2") (pintype "passive"))
    )
    (net (code "28") (name "Net-(C5--)") (class "Default")
      (node (ref "C5") (pin "2") (pinfunction "-_2") (pintype "passive"))
      (node (ref "R11") (pin "2") (pinfunction "2_2") (pintype "passive"))
      (node (ref "R12") (pin "2") (pinfunction "2_2") (pintype "passive"))
      (node (ref "U2") (pin "1") (pinfunction "1OUT_1") (pintype "passive"))
    )
    (net (code "29") (name "Net-(C6--)") (class "Default")
      (node (ref "C6") (pin "2") (pinfunction "-_2") (pintype "passive"))
      (node (ref "R11") (pin "1") (pinfunction "1_1") (pintype "passive"))
      (node (ref "U2") (pin "2") (pinfunction "1IN-_2") (pintype "passive"))
    )
    (net (code "30") (name "Net-(C7-+)") (class "Default")
      (node (ref "C7") (pin "1") (pinfunction "+_1") (pintype "passive"))
      (node (ref "C8") (pin "1") (pinfunction "+_1") (pintype "passive"))
      (node (ref "R12") (pin "1") (pinfunction "1_1") (pintype "passive"))
      (node (ref "R13") (pin "1") (pinfunction "1_1") (pintype "passive"))
    )
    (net (code "31") (name "Net-(C8--)") (class "Default")
      (node (ref "C8") (pin "2") (pinfunction "-_2") (pintype "passive"))
      (node (ref "R14") (pin "2") (pinfunction "2_2") (pintype "passive"))
      (node (ref "U2") (pin "6") (pinfunction "2IN-_6") (pintype "passive"))
    )
    (net (code "32") (name "Net-(C9--)") (class "Default")
      (node (ref "C9") (pin "2") (pinfunction "-_2") (pintype "passive"))
      (node (ref "R19") (pin "2") (pinfunction "2_2") (pintype "passive"))
      (node (ref "R20") (pin "2") (pinfunction "2_2") (pintype "passive"))
      (node (ref "U4") (pin "1") (pinfunction "1OUT_1") (pintype "passive"))
    )
    (net (code "33") (name "Net-(C10-+)") (class "Default")
      (node (ref "C10") (pin "1") (pinfunction "+_1") (pintype "passive"))
      (node (ref "C9") (pin "1") (pinfunction "+_1") (pintype "passive"))
      (node (ref "R17") (pin "2") (pinfunction "2_2") (pintype "passive"))
      (node (ref "R18") (pin "2") (pinfunction "2_2") (pintype "passive"))
    )
    (net (code "34") (name "Net-(C10--)") (class "Default")
      (node (ref "C10") (pin "2") (pinfunction "-_2") (pintype "passive"))
      (node (ref "R19") (pin "1") (pinfunction "1_1") (pintype "passive"))
      (node (ref "U4") (pin "2") (pinfunction "1IN-_2") (pintype "passive"))
    )
    (net (code "35") (name "Net-(C11-+)") (class "Default")
      (node (ref "C11") (pin "1") (pinfunction "+_1") (pintype "passive"))
      (node (ref "C12") (pin "1") (pinfunction "+_1") (pintype "passive"))
      (node (ref "R20") (pin "1") (pinfunction "1_1") (pintype "passive"))
      (node (ref "R21") (pin "1") (pinfunction "1_1") (pintype "passive"))
    )
    (net (code "36") (name "Net-(C12--)") (class "Default")
      (node (ref "C12") (pin "2") (pinfunction "-_2") (pintype "passive"))
      (node (ref "R22") (pin "2") (pinfunction "2_2") (pintype "passive"))
      (node (ref "U4") (pin "6") (pinfunction "2IN-_6") (pintype "passive"))
    )
    (net (code "37") (name "Net-(C13-+)") (class "Default")
      (node (ref "C13") (pin "1") (pinfunction "+_1") (pintype "passive"))
      (node (ref "C14") (pin "1") (pinfunction "+_1") (pintype "passive"))
      (node (ref "R26") (pin "2") (pinfunction "2_2") (pintype "passive"))
      (node (ref "R27") (pin "2") (pinfunction "2_2") (pintype "passive"))
    )
    (net (code "38") (name "Net-(C13--)") (class "Default")
      (node (ref "C13") (pin "2") (pinfunction "-_2") (pintype "passive"))
      (node (ref "R28") (pin "2") (pinfunction "2_2") (pintype "passive"))
      (node (ref "R29") (pin "2") (pinfunction "2_2") (pintype "passive"))
      (node (ref "U5") (pin "1") (pinfunction "1OUT_1") (pintype "passive"))
    )
    (net (code "39") (name "Net-(C14--)") (class "Default")
      (node (ref "C14") (pin "2") (pinfunction "-_2") (pintype "passive"))
      (node (ref "R28") (pin "1") (pinfunction "1_1") (pintype "passive"))
      (node (ref "U5") (pin "2") (pinfunction "1IN-_2") (pintype "passive"))
    )
    (net (code "40") (name "Net-(C15-+)") (class "Default")
      (node (ref "C15") (pin "1") (pinfunction "+_1") (pintype "passive"))
      (node (ref "C16") (pin "1") (pinfunction "+_1") (pintype "passive"))
      (node (ref "R29") (pin "1") (pinfunction "1_1") (pintype "passive"))
      (node (ref "R30") (pin "1") (pinfunction "1_1") (pintype "passive"))
    )
    (net (code "41") (name "Net-(C16--)") (class "Default")
      (node (ref "C16") (pin "2") (pinfunction "-_2") (pintype "passive"))
      (node (ref "R31") (pin "2") (pinfunction "2_2") (pintype "passive"))
      (node (ref "U5") (pin "6") (pinfunction "2IN-_6") (pintype "passive"))
    )
    (net (code "42") (name "Net-(C17-+)") (class "Default")
      (node (ref "C17") (pin "1") (pinfunction "+_1") (pintype "passive"))
      (node (ref "C18") (pin "1") (pinfunction "+_1") (pintype "passive"))
      (node (ref "R34") (pin "2") (pinfunction "2_2") (pintype "passive"))
      (node (ref "R35") (pin "2") (pinfunction "2_2") (pintype "passive"))
    )
    (net (code "43") (name "Net-(C17--)") (class "Default")
      (node (ref "C17") (pin "2") (pinfunction "-_2") (pintype "passive"))
      (node (ref "R36") (pin "2") (pinfunction "2_2") (pintype "passive"))
      (node (ref "R37") (pin "2") (pinfunction "2_2") (pintype "passive"))
      (node (ref "U7") (pin "1") (pinfunction "1OUT_1") (pintype "passive"))
    )
    (net (code "44") (name "Net-(C18--)") (class "Default")
      (node (ref "C18") (pin "2") (pinfunction "-_2") (pintype "passive"))
      (node (ref "R36") (pin "1") (pinfunction "1_1") (pintype "passive"))
      (node (ref "U7") (pin "2") (pinfunction "1IN-_2") (pintype "passive"))
    )
    (net (code "45") (name "Net-(C19-+)") (class "Default")
      (node (ref "C19") (pin "1") (pinfunction "+_1") (pintype "passive"))
      (node (ref "C20") (pin "1") (pinfunction "+_1") (pintype "passive"))
      (node (ref "R37") (pin "1") (pinfunction "1_1") (pintype "passive"))
      (node (ref "R38") (pin "1") (pinfunction "1_1") (pintype "passive"))
    )
    (net (code "46") (name "Net-(C20--)") (class "Default")
      (node (ref "C20") (pin "2") (pinfunction "-_2") (pintype "passive"))
      (node (ref "R39") (pin "2") (pinfunction "2_2") (pintype "passive"))
      (node (ref "U7") (pin "6") (pinfunction "2IN-_6") (pintype "passive"))
    )
    (net (code "47") (name "Net-(J4-Pad2)") (class "Default")
      (node (ref "J4") (pin "2") (pinfunction "2_2") (pintype "passive"))
      (node (ref "R49") (pin "1") (pinfunction "1_1") (pintype "passive"))
    )
    (net (code "48") (name "Net-(U9-1IN+)") (class "Default")
      (node (ref "R48") (pin "1") (pinfunction "1_1") (pintype "passive"))
      (node (ref "R49") (pin "2") (pinfunction "2_2") (pintype "passive"))
      (node (ref "U9") (pin "3") (pinfunction "1IN+_3") (pintype "passive"))
    )
    (net (code "49") (name "Net-(U9-1IN-)") (class "Default")
      (node (ref "R50") (pin "2") (pinfunction "2_2") (pintype "passive"))
      (node (ref "R51") (pin "2") (pinfunction "2_2") (pintype "passive"))
      (node (ref "U9") (pin "2") (pinfunction "1IN-_2") (pintype "passive"))
    )
    (net (code "50") (name "unconnected-(B3-Pad3)") (class "Default")
      (node (ref "B3") (pin "3") (pinfunction "3_3") (pintype "passive"))
    )
    (net (code "51") (name "unconnected-(B4-Pad3)") (class "Default")
      (node (ref "B4") (pin "3") (pinfunction "3_3") (pintype "passive"))
    )
    (net (code "52") (name "unconnected-(B5-Pad3)") (class "Default")
      (node (ref "B5") (pin "3") (pinfunction "3_3") (pintype "passive"))
    )
    (net (code "53") (name "unconnected-(B6-Pad3)") (class "Default")
      (node (ref "B6") (pin "3") (pinfunction "3_3") (pintype "passive"))
    )
    (net (code "54") (name "unconnected-(B7-Pad3)") (class "Default")
      (node (ref "B7") (pin "3") (pinfunction "3_3") (pintype "passive"))
    )
    (net (code "55") (name "unconnected-(B8-Pad3)") (class "Default")
      (node (ref "B8") (pin "3") (pinfunction "3_3") (pintype "passive"))
    )
    (net (code "56") (name "unconnected-(J4-Pad4)") (class "Default")
      (node (ref "J4") (pin "4") (pinfunction "4_4") (pintype "passive"))
    )
    (net (code "57") (name "unconnected-(J4-Pad5)") (class "Default")
      (node (ref "J4") (pin "5") (pinfunction "5_5") (pintype "passive"))
    )
    (net (code "58") (name "unconnected-(J5-Pad4)") (class "Default")
      (node (ref "J5") (pin "4") (pinfunction "4_4") (pintype "passive"))
    )
    (net (code "59") (name "unconnected-(J5-Pad5)") (class "Default")
      (node (ref "J5") (pin "5") (pinfunction "5_5") (pintype "passive"))
    )
    (net (code "60") (name "unconnected-(U9-2OUT-Pad7)") (class "Default")
      (node (ref "U9") (pin "7") (pinfunction "2OUT_7") (pintype "passive"))
    )
  )
)
